# RF_Detector_CD.net
KiCad netlist of a schematic drawn in Altium Designer
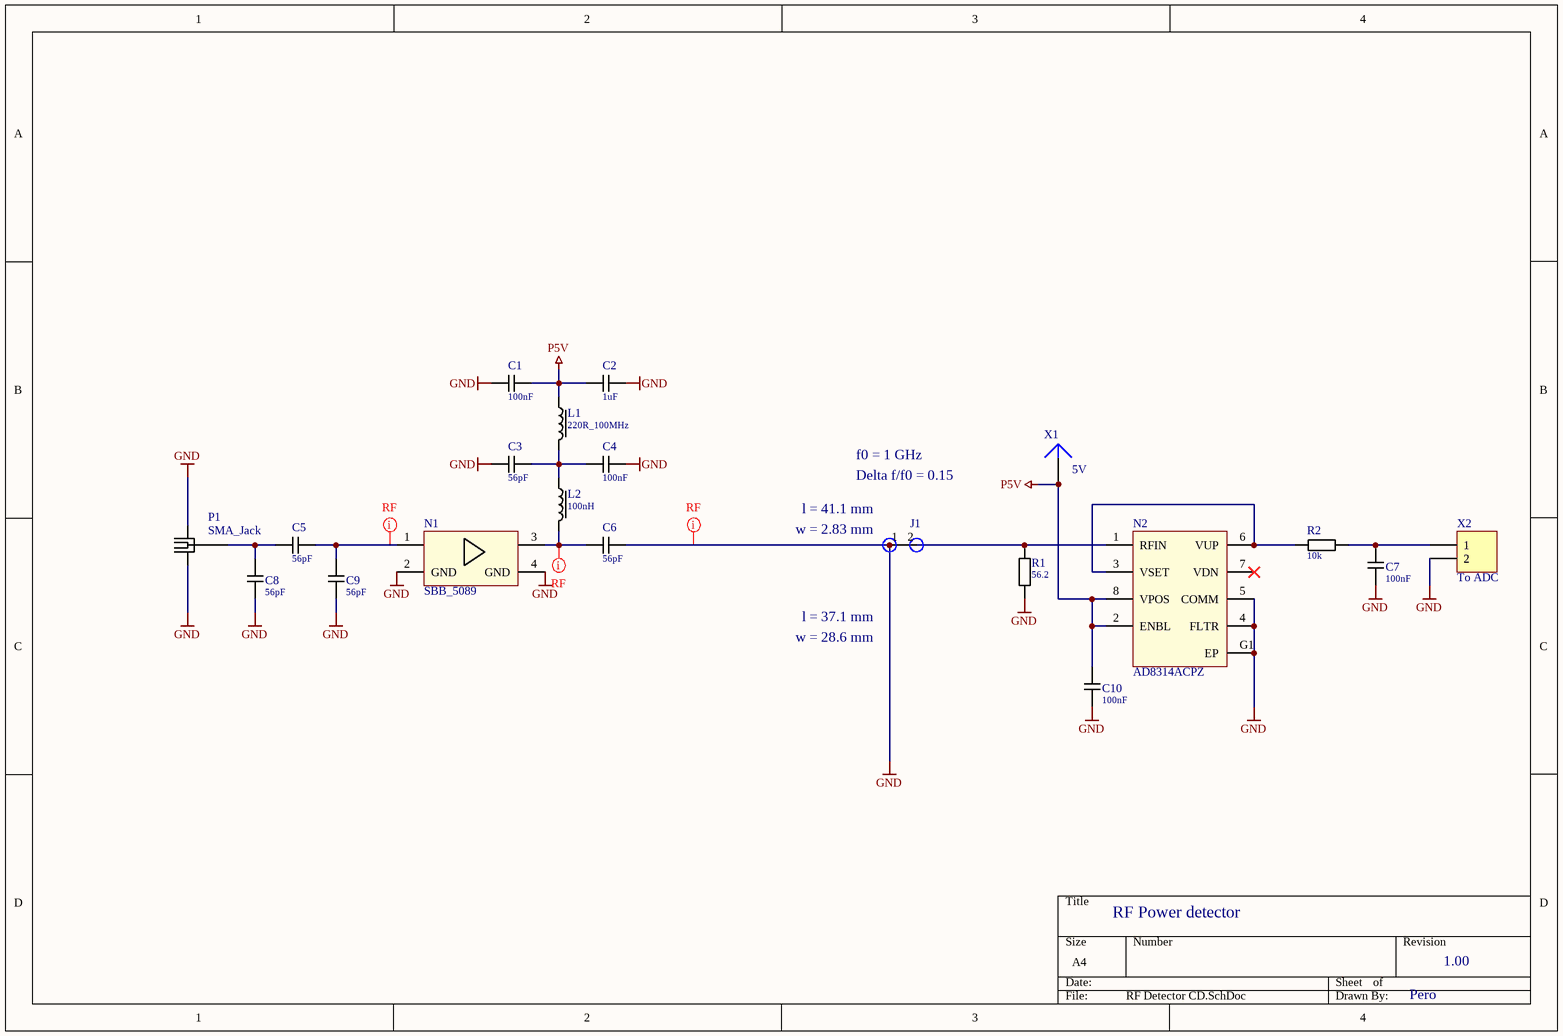
[diagram p0: RF Detector CD.SchDoc]

(export (version "E")
  (design (tool "Eeschema 10.0.6"))
  (components
    (comp (ref "C1")
      (value "100nF")
      (footprint "CAPC1608X90A")
      (description "KERKO 0603 100N 50V 10% X7R")
      (fields
        (field (name "PART_NUMBER") "v39350-z2104-k2")
        (field (name "VOLTAGE") "50V")
        (field (name "CREATOR") "AM")
      )
      (libsource (lib "1001K_Lib") (part "Capacitor"))
    )
    (comp (ref "C2")
      (value "1uF")
      (footprint "CAPC2012X125N")
      (description "KERKO 0805 1U 16V 5% X7R")
      (fields
        (field (name "PART_NUMBER") "v39351-z105-k2")
        (field (name "VOLTAGE") "16V")
        (field (name "CREATOR") "AM")
      )
      (libsource (lib "1001K_Lib") (part "Capacitor"))
    )
    (comp (ref "C3")
      (value "56pF")
      (footprint "CAPC1608X90A")
      (description "KERKO 0603 56P 250V +-1% C0G")
      (fields
        (field (name "PART_NUMBER") "ATC:600S560FT250XT")
        (field (name "VOLTAGE") "250V")
        (field (name "CREATOR") "AM")
      )
      (libsource (lib "1001K_Lib") (part "Capacitor"))
    )
    (comp (ref "C4")
      (value "100nF")
      (footprint "CAPC1608X90A")
      (description "KERKO 0603 100N 50V 10% X7R")
      (fields
        (field (name "PART_NUMBER") "v39350-z2104-k2")
        (field (name "VOLTAGE") "50V")
        (field (name "CREATOR") "AM")
      )
      (libsource (lib "1001K_Lib") (part "Capacitor"))
    )
    (comp (ref "C5")
      (value "56pF")
      (footprint "CAPC1608X90A")
      (description "KERKO 0603 56P 250V +-1% C0G")
      (fields
        (field (name "PART_NUMBER") "ATC:600S560FT250XT")
        (field (name "VOLTAGE") "250V")
        (field (name "CREATOR") "AM")
      )
      (libsource (lib "1001K_Lib") (part "Capacitor"))
    )
    (comp (ref "C6")
      (value "56pF")
      (footprint "CAPC1608X90A")
      (description "KERKO 0603 56P 250V +-1% C0G")
      (fields
        (field (name "PART_NUMBER") "ATC:600S560FT250XT")
        (field (name "VOLTAGE") "250V")
        (field (name "CREATOR") "AM")
      )
      (libsource (lib "1001K_Lib") (part "Capacitor"))
    )
    (comp (ref "C7")
      (value "100nF")
      (footprint "CAPC1608X90A")
      (description "KERKO 0603 100N 50V 10% X7R")
      (fields
        (field (name "PART_NUMBER") "v39350-z2104-k2")
        (field (name "VOLTAGE") "50V")
        (field (name "CREATOR") "AM")
      )
      (libsource (lib "1001K_Lib") (part "Capacitor"))
    )
    (comp (ref "C8")
      (value "56pF")
      (footprint "CAPC1608X90A")
      (description "KERKO 0603 56P 250V +-1% C0G")
      (fields
        (field (name "PART_NUMBER") "ATC:600S560FT250XT")
        (field (name "VOLTAGE") "250V")
        (field (name "CREATOR") "AM")
      )
      (libsource (lib "1001K_Lib") (part "Capacitor"))
    )
    (comp (ref "C9")
      (value "56pF")
      (footprint "CAPC1608X90A")
      (description "KERKO 0603 56P 250V +-1% C0G")
      (fields
        (field (name "PART_NUMBER") "ATC:600S560FT250XT")
        (field (name "VOLTAGE") "250V")
        (field (name "CREATOR") "AM")
      )
      (libsource (lib "1001K_Lib") (part "Capacitor"))
    )
    (comp (ref "C10")
      (value "100nF")
      (footprint "CAPC1608X90A")
      (description "KERKO 0603 100N 50V 10% X7R")
      (fields
        (field (name "PART_NUMBER") "v39350-z2104-k2")
        (field (name "VOLTAGE") "50V")
        (field (name "CREATOR") "AM")
      )
      (libsource (lib "1001K_Lib") (part "Capacitor"))
    )
    (comp (ref "J1")
      (value "~")
      (footprint "SMDCUT_2_0.3_1.27_-_RR")
      (description "Special SMD Cut component")
      (fields (field (name "PART_NUMBER") "CUTSMD-WIDTH0.3MM"))
      (libsource (lib "1001K_Lib") (part "cut_all_v1"))
    )
    (comp (ref "L1")
      (value "220R_100MHz")
      (footprint "INDC1608X90A")
      (description "FERRIT 0603 220R 100MHZ 2A DCR=0R05")
      (fields
        (field (name "PART_NUMBER") "v50010-g96-a1")
        (field (name "COMMERCIAL_PART") "BLM18EG221SN1D")
        (field (name "CREATOR") "AM")
      )
      (libsource (lib "1001K_Lib") (part "Ferrite"))
    )
    (comp (ref "L2")
      (value "100nH")
      (footprint "INDP1609X94L")
      (description "DROSSEL SMD 0603 100N 0A22 2%")
      (fields
        (field (name "PART_NUMBER") "V50010-G27-A5")
        (field (name "COMMERCIAL_PART") "LQW18ANR10G00D")
        (field (name "CREATOR") "AM")
      )
      (libsource (lib "1001K_Lib") (part "Ferrite"))
    )
    (comp (ref "N1")
      (value "SBB_5089")
      (footprint "SMD_SOT89-4_4.6x4.25_1.5")
      (description "50MHz to 6000MHz, CASCADABLE ACTIVE BIAS InGaP HBT MMIC AMPLIFIER")
      (fields (field (name "PART_NUMBER") "SIRENZA:SBB_5089") (field (name "CREATOR") "AM"))
      (libsource (lib "1001K_Lib") (part "SBB_5089"))
    )
    (comp (ref "N2")
      (value "AD8314ACPZ")
      (footprint "ANALOG_LFCSP_VD_CP-8-1TN")
      (description "100 MHz to 2.7 GHz, 45 dB RF Detector/Controller")
      (fields (field (name "PART_NUMBER") "ANALOG_DEVICES:AD8314ACP") (field (name "CREATOR") "AM"))
      (libsource (lib "1001K_Lib") (part "AD8314acp_EP"))
    )
    (comp (ref "P1")
      (value "SMA_Jack")
      (footprint "SMA_Jack_7x7x14mm")
      (description "SMA Jack edge mounted")
      (fields
        (field (name "PART_NUMBER") "RSCOMPONENTS:SMA_Jack")
        (field (name "COMMERCIAL_PART") "SMA_JACK")
        (field (name "CREATOR") "HD")
      )
      (libsource (lib "1001K_Lib") (part "SMA_Jack"))
    )
    (comp (ref "R1")
      (value "56.2")
      (footprint "RESC1608X45A")
      (description "WID CHIP 0603 56R2 1% TK100")
      (fields (field (name "PART_NUMBER") "v39244-z5560-f200") (field (name "TOLERANCE") "1%"))
      (libsource (lib "1001K_Lib") (part "Resistor"))
    )
    (comp (ref "R2")
      (value "10k")
      (footprint "RESC1608X45A")
      (description "WID CHIP 0603 10K 1% TK100")
      (fields (field (name "PART_NUMBER") "v39244-z5103-f") (field (name "TOLERANCE") "1%"))
      (libsource (lib "1001K_Lib") (part "Resistor"))
    )
    (comp (ref "X1")
      (value "5V")
      (footprint "PIN1")
      (description "Plug")
      (fields (field (name "PUBLISHER") "Altium Limited"))
      (libsource (lib "Miscellaneous Connectors") (part "Plug"))
    )
    (comp (ref "X2")
      (value "To ADC")
      (footprint "HDR1X2")
      (description "Header, 2-Pin")
      (fields (field (name "PUBLISHER") "Altium Limited"))
      (libsource (lib "Miscellaneous Connectors") (part "Header 2"))
    )
  )
  (nets
    (net (code "1") (name "GND") (class "Default")
      (node (ref "C1") (pin "1") (pinfunction "1_1") (pintype "passive"))
      (node (ref "C10") (pin "2") (pinfunction "2_2") (pintype "passive"))
      (node (ref "C2") (pin "2") (pinfunction "2_2") (pintype "passive"))
      (node (ref "C3") (pin "1") (pinfunction "1_1") (pintype "passive"))
      (node (ref "C4") (pin "2") (pinfunction "2_2") (pintype "passive"))
      (node (ref "C6") (pin "2") (pinfunction "2_2") (pintype "passive"))
      (node (ref "C7") (pin "2") (pinfunction "2_2") (pintype "passive"))
      (node (ref "C8") (pin "2") (pinfunction "2_2") (pintype "passive"))
      (node (ref "C9") (pin "1") (pinfunction "1_1") (pintype "passive"))
      (node (ref "J1") (pin "1") (pinfunction "1_1") (pintype "passive"))
      (node (ref "N1") (pin "2") (pinfunction "GND_2") (pintype "power_in"))
      (node (ref "N1") (pin "4") (pinfunction "GND_4") (pintype "power_in"))
      (node (ref "N2") (pin "4") (pinfunction "FLTR_4") (pintype "passive"))
      (node (ref "N2") (pin "5") (pinfunction "COMM_5") (pintype "power_in"))
      (node (ref "N2") (pin "G1") (pinfunction "EP_G1") (pintype "power_in"))
      (node (ref "P1") (pin "2") (pinfunction "GND_2") (pintype "power_in"))
      (node (ref "P1") (pin "3") (pinfunction "GND_3") (pintype "power_in"))
      (node (ref "R1") (pin "2") (pinfunction "2_2") (pintype "passive"))
      (node (ref "X2") (pin "2") (pinfunction "2_2") (pintype "passive"))
    )
    (net (code "2") (name "Net-(C3-Pad2)") (class "Default")
      (node (ref "C3") (pin "2") (pinfunction "2_2") (pintype "passive"))
      (node (ref "C4") (pin "1") (pinfunction "1_1") (pintype "passive"))
      (node (ref "L1") (pin "2") (pinfunction "2_2") (pintype "passive"))
      (node (ref "L2") (pin "1") (pinfunction "1_1") (pintype "passive"))
    )
    (net (code "3") (name "Net-(C5-Pad2)") (class "Default")
      (node (ref "C5") (pin "2") (pinfunction "2_2") (pintype "passive"))
      (node (ref "C9") (pin "2") (pinfunction "2_2") (pintype "passive"))
      (node (ref "N1") (pin "1") (pintype "passive"))
    )
    (net (code "4") (name "Net-(C6-Pad1)") (class "Default")
      (node (ref "C6") (pin "1") (pinfunction "1_1") (pintype "passive"))
      (node (ref "L2") (pin "2") (pinfunction "2_2") (pintype "passive"))
      (node (ref "N1") (pin "3") (pintype "passive"))
    )
    (net (code "5") (name "Net-(C7-Pad1)") (class "Default")
      (node (ref "C7") (pin "1") (pinfunction "1_1") (pintype "passive"))
      (node (ref "R2") (pin "2") (pinfunction "2_2") (pintype "passive"))
      (node (ref "X2") (pin "1") (pinfunction "1_1") (pintype "passive"))
    )
    (net (code "6") (name "Net-(N2-RFIN)") (class "Default")
      (node (ref "J1") (pin "2") (pinfunction "2_2") (pintype "passive"))
      (node (ref "N2") (pin "1") (pinfunction "RFIN_1") (pintype "passive"))
      (node (ref "R1") (pin "1") (pinfunction "1_1") (pintype "passive"))
    )
    (net (code "7") (name "Net-(N2-VSET)") (class "Default")
      (node (ref "N2") (pin "3") (pinfunction "VSET_3") (pintype "passive"))
      (node (ref "N2") (pin "6") (pinfunction "VUP_6") (pintype "passive"))
      (node (ref "R2") (pin "1") (pinfunction "1_1") (pintype "passive"))
    )
    (net (code "8") (name "Net-(P1-SMA)") (class "Default")
      (node (ref "C5") (pin "1") (pinfunction "1_1") (pintype "passive"))
      (node (ref "C8") (pin "1") (pinfunction "1_1") (pintype "passive"))
      (node (ref "P1") (pin "1") (pinfunction "SMA_1") (pintype "passive"))
    )
    (net (code "9") (name "P5V") (class "Default")
      (node (ref "C1") (pin "2") (pinfunction "2_2") (pintype "passive"))
      (node (ref "C10") (pin "1") (pinfunction "1_1") (pintype "passive"))
      (node (ref "C2") (pin "1") (pinfunction "1_1") (pintype "passive"))
      (node (ref "L1") (pin "1") (pinfunction "1_1") (pintype "passive"))
      (node (ref "N2") (pin "2") (pinfunction "ENBL_2") (pintype "passive"))
      (node (ref "N2") (pin "8") (pinfunction "VPOS_8") (pintype "passive"))
      (node (ref "X1") (pin "1") (pinfunction "1_1") (pintype "passive"))
    )
    (net (code "10") (name "unconnected-(N2-VDN-Pad7)") (class "Default")
      (node (ref "N2") (pin "7") (pinfunction "VDN_7") (pintype "passive+no_connect"))
    )
  )
)
